# mcu.net
KiCad netlist of a schematic drawn in Altium Designer
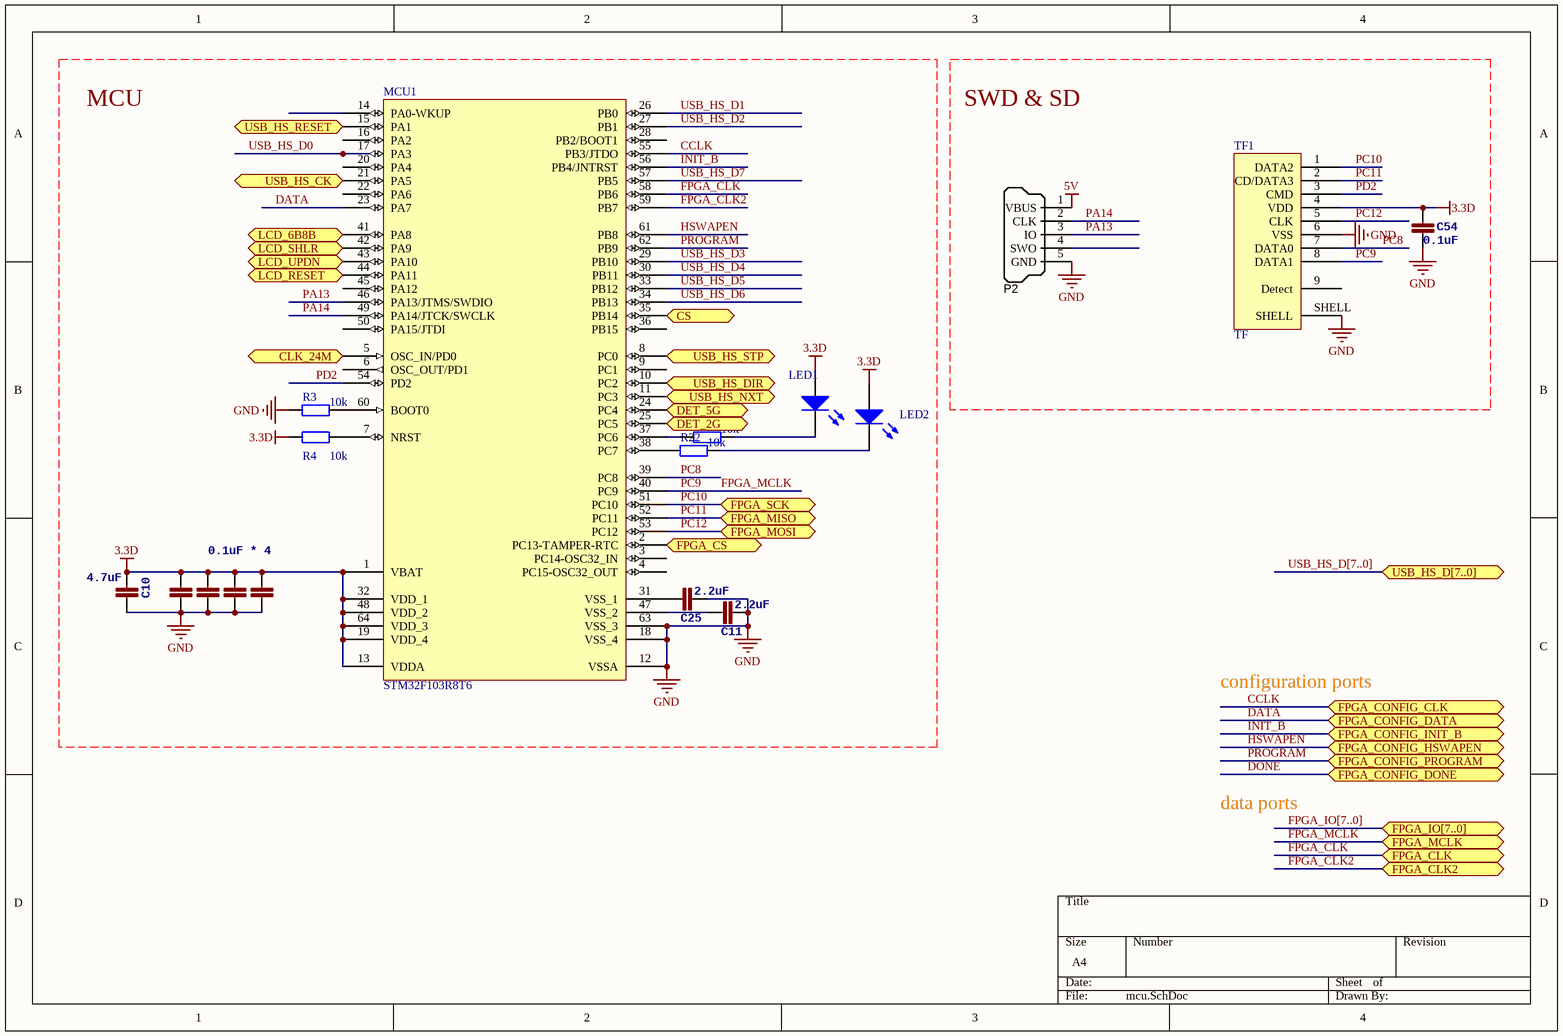
[diagram p0: mcu.SchDoc]

(export (version "E")
  (design (tool "Eeschema 10.0.6"))
  (components
    (comp (ref "C4")
      (value "0.1uF * 4")
      (footprint "0402")
      (description "<b>Capacitor</b>\nStandard 0603 ceramic capacitor, and 0.1\" leaded capacitor.")
      (fields (field (name "PARTNO") "CC0402ZRY5V7BB104"))
      (libsource (lib "*") (part "CAP0402-CAP"))
    )
    (comp (ref "C5")
      (value "1n")
      (footprint "0402")
      (description "<b>Capacitor</b>\nStandard 0603 ceramic capacitor, and 0.1\" leaded capacitor.")
      (fields (field (name "PARTNO") "CC0402ZRY5V7BB104"))
      (libsource (lib "pixhawk2") (part "CAP0402-CAP"))
    )
    (comp (ref "C6")
      (value "1n")
      (footprint "0402")
      (description "<b>Capacitor</b>\nStandard 0603 ceramic capacitor, and 0.1\" leaded capacitor.")
      (fields (field (name "PARTNO") "CC0402ZRY5V7BB104"))
      (libsource (lib "pixhawk2") (part "CAP0402-CAP"))
    )
    (comp (ref "C7")
      (value "1n")
      (footprint "0402")
      (description "<b>Capacitor</b>\nStandard 0603 ceramic capacitor, and 0.1\" leaded capacitor.")
      (fields (field (name "PARTNO") "CC0402ZRY5V7BB104"))
      (libsource (lib "pixhawk2") (part "CAP0402-CAP"))
    )
    (comp (ref "C10")
      (value "4.7uF")
      (footprint "0603")
      (description "<b>Capacitor</b>\nStandard 0603 ceramic capacitor, and 0.1\" leaded capacitor.")
      (fields (field (name "PARTNO") "CC0402ZRY5V7BB104"))
      (libsource (lib "pixhawk2") (part "CAP0402-CAP"))
    )
    (comp (ref "C11")
      (value "2.2uF")
      (footprint "0603")
      (description "<b>Capacitor</b>\nStandard 0603 ceramic capacitor, and 0.1\" leaded capacitor.")
      (fields (field (name "PARTNO") "CC0402ZRY5V7BB104"))
      (libsource (lib "") (part "CAP0402-CAP_1"))
    )
    (comp (ref "C25")
      (value "2.2uF")
      (footprint "0603")
      (description "<b>Capacitor</b>\nStandard 0603 ceramic capacitor, and 0.1\" leaded capacitor.")
      (fields (field (name "PARTNO") "CC0402ZRY5V7BB104"))
      (libsource (lib "") (part "CAP0402-CAP_1"))
    )
    (comp (ref "C54")
      (value "0.1uF")
      (footprint "0402")
      (description "<b>Capacitor</b>\nStandard 0603 ceramic capacitor, and 0.1\" leaded capacitor.")
      (fields (field (name "PARTNO") "CC0402ZRY5V7BB104"))
      (libsource (lib "pixhawk2") (part "CAP0402-CAP"))
    )
    (comp (ref "LED1")
      (value "LED0")
      (footprint "0603")
      (description "Typical INFRARED GaAs LED")
      (fields (field (name "PUBLISHER") "Altium Limited"))
      (libsource (lib "Miscellaneous Devices") (part "LED0"))
    )
    (comp (ref "LED2")
      (value "LED0")
      (footprint "0603")
      (description "Typical INFRARED GaAs LED")
      (fields (field (name "PUBLISHER") "Altium Limited"))
      (libsource (lib "Miscellaneous Devices") (part "LED0"))
    )
    (comp (ref "MCU1")
      (value "STM32F103R8T6")
      (footprint "LQFP64_N")
      (description "STM32 ARM-based 32-bit MCU with 64 Kbytes Flash, 64-pin LQFP, Industrial Temperature")
      (fields (field (name "PUBLISHER") "*"))
      (libsource (lib "ST Microcontroller 32-Bit STM32 SCH") (part "STM32F103R8T6"))
    )
    (comp (ref "P2")
      (value "SWD_MicroUSB")
      (footprint "MICRO-YZX")
      (description "Connector SMD USB Micro Type B middle mount")
      (libsource (lib "sch") (part "SWD_MicroUSB"))
    )
    (comp (ref "R3")
      (value "10k")
      (footprint "0402")
      (description "Resistor")
      (fields (field (name "PUBLISHER") "Altium Limited"))
      (libsource (lib "Miscellaneous Devices") (part "Res2"))
    )
    (comp (ref "R4")
      (value "10k")
      (footprint "0402")
      (description "Resistor")
      (fields (field (name "PUBLISHER") "Altium Limited"))
      (libsource (lib "") (part "Res2_1"))
    )
    (comp (ref "R21")
      (value "10k")
      (footprint "0402")
      (description "Resistor")
      (fields (field (name "PUBLISHER") "Altium Limited"))
      (libsource (lib "Miscellaneous Devices") (part "Res2"))
    )
    (comp (ref "R22")
      (value "10k")
      (footprint "0402")
      (description "Resistor")
      (fields (field (name "PUBLISHER") "Altium Limited"))
      (libsource (lib "Miscellaneous Devices") (part "Res2"))
    )
    (comp (ref "TF1") (value "TF") (footprint "TF") (libsource (lib "complements") (part "TF")))
  )
  (nets
    (net (code "9") (name "/CCLK") (class "Default")
      (node (ref "MCU1") (pin "55") (pinfunction "PB3/JTDO_55") (pintype "bidirectional"))
    )
    (net (code "10") (name "/CLK_24M") (class "Default")
      (node (ref "MCU1") (pin "5") (pinfunction "OSC_IN/PD0_5") (pintype "input"))
    )
    (net (code "11") (name "/CS") (class "Default")
      (node (ref "MCU1") (pin "35") (pinfunction "PB14_35") (pintype "bidirectional"))
    )
    (net (code "12") (name "/DATA") (class "Default")
      (node (ref "MCU1") (pin "23") (pinfunction "PA7_23") (pintype "bidirectional"))
    )
    (net (code "13") (name "/DET_2G") (class "Default")
      (node (ref "MCU1") (pin "25") (pinfunction "PC5_25") (pintype "bidirectional"))
    )
    (net (code "14") (name "/DET_5G") (class "Default")
      (node (ref "MCU1") (pin "24") (pinfunction "PC4_24") (pintype "bidirectional"))
    )
    (net (code "16") (name "/FPGA_CLK") (class "Default")
      (node (ref "MCU1") (pin "58") (pinfunction "PB6_58") (pintype "bidirectional"))
    )
    (net (code "17") (name "/FPGA_CLK2") (class "Default")
      (node (ref "MCU1") (pin "59") (pinfunction "PB7_59") (pintype "bidirectional"))
    )
    (net (code "18") (name "/FPGA_CS") (class "Default")
      (node (ref "MCU1") (pin "2") (pinfunction "PC13-TAMPER-RTC_2") (pintype "bidirectional"))
    )
    (net (code "20") (name "/FPGA_MCLK") (class "Default")
      (node (ref "MCU1") (pin "40") (pinfunction "PC9_40") (pintype "bidirectional"))
      (node (ref "TF1") (pin "8") (pinfunction "DATA1_8") (pintype "passive"))
    )
    (net (code "21") (name "/HSWAPEN") (class "Default")
      (node (ref "MCU1") (pin "61") (pinfunction "PB8_61") (pintype "bidirectional"))
    )
    (net (code "22") (name "/INIT_B") (class "Default")
      (node (ref "MCU1") (pin "56") (pinfunction "PB4/JNTRST_56") (pintype "bidirectional"))
    )
    (net (code "23") (name "/LCD_6B8B") (class "Default")
      (node (ref "MCU1") (pin "41") (pinfunction "PA8_41") (pintype "bidirectional"))
    )
    (net (code "24") (name "/LCD_RESET") (class "Default")
      (node (ref "MCU1") (pin "44") (pinfunction "PA11_44") (pintype "bidirectional"))
    )
    (net (code "25") (name "/LCD_SHLR") (class "Default")
      (node (ref "MCU1") (pin "42") (pinfunction "PA9_42") (pintype "bidirectional"))
    )
    (net (code "26") (name "/LCD_UPDN") (class "Default")
      (node (ref "MCU1") (pin "43") (pinfunction "PA10_43") (pintype "bidirectional"))
    )
    (net (code "27") (name "/PA13") (class "Default")
      (node (ref "MCU1") (pin "46") (pinfunction "PA13/JTMS/SWDIO_46") (pintype "bidirectional"))
      (node (ref "P2") (pin "3") (pinfunction "IO_3") (pintype "passive"))
    )
    (net (code "28") (name "/PA14") (class "Default")
      (node (ref "MCU1") (pin "49") (pinfunction "PA14/JTCK/SWCLK_49") (pintype "bidirectional"))
      (node (ref "P2") (pin "2") (pinfunction "CLK_2") (pintype "passive"))
    )
    (net (code "29") (name "/PC8") (class "Default")
      (node (ref "MCU1") (pin "39") (pinfunction "PC8_39") (pintype "bidirectional"))
      (node (ref "TF1") (pin "7") (pinfunction "DATA0_7") (pintype "passive"))
    )
    (net (code "30") (name "/PC10") (class "Default")
      (node (ref "MCU1") (pin "51") (pinfunction "PC10_51") (pintype "bidirectional"))
      (node (ref "TF1") (pin "1") (pinfunction "DATA2_1") (pintype "passive"))
    )
    (net (code "31") (name "/PC11") (class "Default")
      (node (ref "MCU1") (pin "52") (pinfunction "PC11_52") (pintype "bidirectional"))
      (node (ref "TF1") (pin "2") (pinfunction "CD/DATA3_2") (pintype "passive"))
    )
    (net (code "32") (name "/PC12") (class "Default")
      (node (ref "MCU1") (pin "53") (pinfunction "PC12_53") (pintype "bidirectional"))
      (node (ref "TF1") (pin "5") (pinfunction "CLK_5") (pintype "passive"))
    )
    (net (code "33") (name "/PD2") (class "Default")
      (node (ref "MCU1") (pin "54") (pinfunction "PD2_54") (pintype "bidirectional"))
      (node (ref "TF1") (pin "3") (pinfunction "CMD_3") (pintype "passive"))
    )
    (net (code "34") (name "/PROGRAM") (class "Default")
      (node (ref "MCU1") (pin "62") (pinfunction "PB9_62") (pintype "bidirectional"))
    )
    (net (code "35") (name "/USB_HS_CK") (class "Default")
      (node (ref "MCU1") (pin "21") (pinfunction "PA5_21") (pintype "bidirectional"))
    )
    (net (code "36") (name "/USB_HS_D0") (class "Default")
      (node (ref "MCU1") (pin "17") (pinfunction "PA3_17") (pintype "bidirectional"))
    )
    (net (code "37") (name "/USB_HS_D1") (class "Default")
      (node (ref "MCU1") (pin "26") (pinfunction "PB0_26") (pintype "bidirectional"))
    )
    (net (code "38") (name "/USB_HS_D2") (class "Default")
      (node (ref "MCU1") (pin "27") (pinfunction "PB1_27") (pintype "bidirectional"))
    )
    (net (code "39") (name "/USB_HS_D3") (class "Default")
      (node (ref "MCU1") (pin "29") (pinfunction "PB10_29") (pintype "bidirectional"))
    )
    (net (code "40") (name "/USB_HS_D4") (class "Default")
      (node (ref "MCU1") (pin "30") (pinfunction "PB11_30") (pintype "bidirectional"))
    )
    (net (code "41") (name "/USB_HS_D5") (class "Default")
      (node (ref "MCU1") (pin "33") (pinfunction "PB12_33") (pintype "bidirectional"))
    )
    (net (code "42") (name "/USB_HS_D6") (class "Default")
      (node (ref "MCU1") (pin "34") (pinfunction "PB13_34") (pintype "bidirectional"))
    )
    (net (code "43") (name "/USB_HS_D7") (class "Default")
      (node (ref "MCU1") (pin "57") (pinfunction "PB5_57") (pintype "bidirectional"))
    )
    (net (code "44") (name "/USB_HS_DIR") (class "Default")
      (node (ref "MCU1") (pin "10") (pinfunction "PC2_10") (pintype "bidirectional"))
    )
    (net (code "46") (name "/USB_HS_NXT") (class "Default")
      (node (ref "MCU1") (pin "11") (pinfunction "PC3_11") (pintype "bidirectional"))
    )
    (net (code "47") (name "/USB_HS_RESET") (class "Default")
      (node (ref "MCU1") (pin "15") (pinfunction "PA1_15") (pintype "bidirectional"))
    )
    (net (code "48") (name "/USB_HS_STP") (class "Default")
      (node (ref "MCU1") (pin "8") (pinfunction "PC0_8") (pintype "bidirectional"))
    )
    (net (code "49") (name "3.3D") (class "Default")
      (node (ref "C10") (pin "2") (pinfunction "2_2") (pintype "passive"))
      (node (ref "C4") (pin "2") (pinfunction "2_2") (pintype "passive"))
      (node (ref "C5") (pin "2") (pinfunction "2_2") (pintype "passive"))
      (node (ref "C54") (pin "2") (pinfunction "2_2") (pintype "passive"))
      (node (ref "C6") (pin "2") (pinfunction "2_2") (pintype "passive"))
      (node (ref "C7") (pin "2") (pinfunction "2_2") (pintype "passive"))
      (node (ref "LED1") (pin "1") (pinfunction "A_1") (pintype "passive"))
      (node (ref "LED2") (pin "1") (pinfunction "A_1") (pintype "passive"))
      (node (ref "MCU1") (pin "1") (pinfunction "VBAT_1") (pintype "power_in"))
      (node (ref "MCU1") (pin "13") (pinfunction "VDDA_13") (pintype "power_in"))
      (node (ref "MCU1") (pin "19") (pinfunction "VDD_4_19") (pintype "power_in"))
      (node (ref "MCU1") (pin "32") (pinfunction "VDD_1_32") (pintype "power_in"))
      (node (ref "MCU1") (pin "48") (pinfunction "VDD_2_48") (pintype "power_in"))
      (node (ref "MCU1") (pin "64") (pinfunction "VDD_3_64") (pintype "power_in"))
      (node (ref "R4") (pin "2") (pinfunction "2_2") (pintype "passive"))
      (node (ref "TF1") (pin "4") (pinfunction "VDD_4") (pintype "passive"))
    )
    (net (code "50") (name "5V") (class "Default")
      (node (ref "P2") (pin "1") (pinfunction "VBUS_1") (pintype "passive"))
    )
    (net (code "51") (name "GND") (class "Default")
      (node (ref "C10") (pin "1") (pinfunction "1_1") (pintype "passive"))
      (node (ref "C11") (pin "2") (pinfunction "2_2") (pintype "passive"))
      (node (ref "C25") (pin "2") (pinfunction "2_2") (pintype "passive"))
      (node (ref "C4") (pin "1") (pinfunction "1_1") (pintype "passive"))
      (node (ref "C5") (pin "1") (pinfunction "1_1") (pintype "passive"))
      (node (ref "C54") (pin "1") (pinfunction "1_1") (pintype "passive"))
      (node (ref "C6") (pin "1") (pinfunction "1_1") (pintype "passive"))
      (node (ref "C7") (pin "1") (pinfunction "1_1") (pintype "passive"))
      (node (ref "MCU1") (pin "12") (pinfunction "VSSA_12") (pintype "power_in"))
      (node (ref "MCU1") (pin "18") (pinfunction "VSS_4_18") (pintype "power_in"))
      (node (ref "MCU1") (pin "63") (pinfunction "VSS_3_63") (pintype "power_in"))
      (node (ref "P2") (pin "5") (pinfunction "GND_5") (pintype "passive"))
      (node (ref "R3") (pin "1") (pinfunction "1_1") (pintype "passive"))
      (node (ref "TF1") (pin "6") (pinfunction "VSS_6") (pintype "passive"))
      (node (ref "TF1") (pin "SHELL") (pinfunction "SHELL_SHELL") (pintype "passive"))
    )
    (net (code "52") (name "Net-(LED1-K)") (class "Default")
      (node (ref "LED1") (pin "2") (pinfunction "K_2") (pintype "passive"))
      (node (ref "R21") (pin "2") (pinfunction "2_2") (pintype "passive"))
    )
    (net (code "53") (name "Net-(LED2-K)") (class "Default")
      (node (ref "LED2") (pin "2") (pinfunction "K_2") (pintype "passive"))
      (node (ref "R22") (pin "2") (pinfunction "2_2") (pintype "passive"))
    )
    (net (code "54") (name "Net-(MCU1-BOOT0)") (class "Default")
      (node (ref "MCU1") (pin "60") (pinfunction "BOOT0_60") (pintype "input"))
      (node (ref "R3") (pin "2") (pinfunction "2_2") (pintype "passive"))
    )
    (net (code "55") (name "Net-(MCU1-NRST)") (class "Default")
      (node (ref "MCU1") (pin "7") (pinfunction "NRST_7") (pintype "bidirectional"))
      (node (ref "R4") (pin "1") (pinfunction "1_1") (pintype "passive"))
    )
    (net (code "56") (name "Net-(MCU1-PC6)") (class "Default")
      (node (ref "MCU1") (pin "37") (pinfunction "PC6_37") (pintype "bidirectional"))
      (node (ref "R21") (pin "1") (pinfunction "1_1") (pintype "passive"))
    )
    (net (code "57") (name "Net-(MCU1-PC7)") (class "Default")
      (node (ref "MCU1") (pin "38") (pinfunction "PC7_38") (pintype "bidirectional"))
      (node (ref "R22") (pin "1") (pinfunction "1_1") (pintype "passive"))
    )
    (net (code "58") (name "Net-(MCU1-VSS_1)") (class "Default")
      (node (ref "C25") (pin "1") (pinfunction "1_1") (pintype "passive"))
      (node (ref "MCU1") (pin "31") (pinfunction "VSS_1_31") (pintype "power_in"))
    )
    (net (code "59") (name "Net-(MCU1-VSS_2)") (class "Default")
      (node (ref "C11") (pin "1") (pinfunction "1_1") (pintype "passive"))
      (node (ref "MCU1") (pin "47") (pinfunction "VSS_2_47") (pintype "power_in"))
    )
    (net (code "60") (name "unconnected-(MCU1-OSC_OUT{slash}PD1-Pad6)") (class "Default")
      (node (ref "MCU1") (pin "6") (pinfunction "OSC_OUT/PD1_6") (pintype "output"))
    )
    (net (code "61") (name "unconnected-(MCU1-PA0-WKUP-Pad14)") (class "Default")
      (node (ref "MCU1") (pin "14") (pinfunction "PA0-WKUP_14") (pintype "bidirectional"))
    )
    (net (code "62") (name "unconnected-(MCU1-PA2-Pad16)") (class "Default")
      (node (ref "MCU1") (pin "16") (pinfunction "PA2_16") (pintype "bidirectional"))
    )
    (net (code "63") (name "unconnected-(MCU1-PA4-Pad20)") (class "Default")
      (node (ref "MCU1") (pin "20") (pinfunction "PA4_20") (pintype "bidirectional"))
    )
    (net (code "64") (name "unconnected-(MCU1-PA6-Pad22)") (class "Default")
      (node (ref "MCU1") (pin "22") (pinfunction "PA6_22") (pintype "bidirectional"))
    )
    (net (code "65") (name "unconnected-(MCU1-PA12-Pad45)") (class "Default")
      (node (ref "MCU1") (pin "45") (pinfunction "PA12_45") (pintype "bidirectional"))
    )
    (net (code "66") (name "unconnected-(MCU1-PA15{slash}JTDI-Pad50)") (class "Default")
      (node (ref "MCU1") (pin "50") (pinfunction "PA15/JTDI_50") (pintype "bidirectional"))
    )
    (net (code "67") (name "unconnected-(MCU1-PB2{slash}BOOT1-Pad28)") (class "Default")
      (node (ref "MCU1") (pin "28") (pinfunction "PB2/BOOT1_28") (pintype "bidirectional"))
    )
    (net (code "68") (name "unconnected-(MCU1-PB15-Pad36)") (class "Default")
      (node (ref "MCU1") (pin "36") (pinfunction "PB15_36") (pintype "bidirectional"))
    )
    (net (code "69") (name "unconnected-(MCU1-PC1-Pad9)") (class "Default")
      (node (ref "MCU1") (pin "9") (pinfunction "PC1_9") (pintype "bidirectional"))
    )
    (net (code "70") (name "unconnected-(MCU1-PC14-OSC32_IN-Pad3)") (class "Default")
      (node (ref "MCU1") (pin "3") (pinfunction "PC14-OSC32_IN_3") (pintype "bidirectional"))
    )
    (net (code "71") (name "unconnected-(MCU1-PC15-OSC32_OUT-Pad4)") (class "Default")
      (node (ref "MCU1") (pin "4") (pinfunction "PC15-OSC32_OUT_4") (pintype "bidirectional"))
    )
    (net (code "72") (name "unconnected-(P2-SWO-Pad4)") (class "Default")
      (node (ref "P2") (pin "4") (pinfunction "SWO_4") (pintype "passive"))
    )
    (net (code "73") (name "unconnected-(TF1-Detect-Pad9)") (class "Default")
      (node (ref "TF1") (pin "9") (pinfunction "Detect_9") (pintype "passive"))
    )
  )
)
